# POESP32.net
KiCad netlist of a schematic drawn in EAGLE
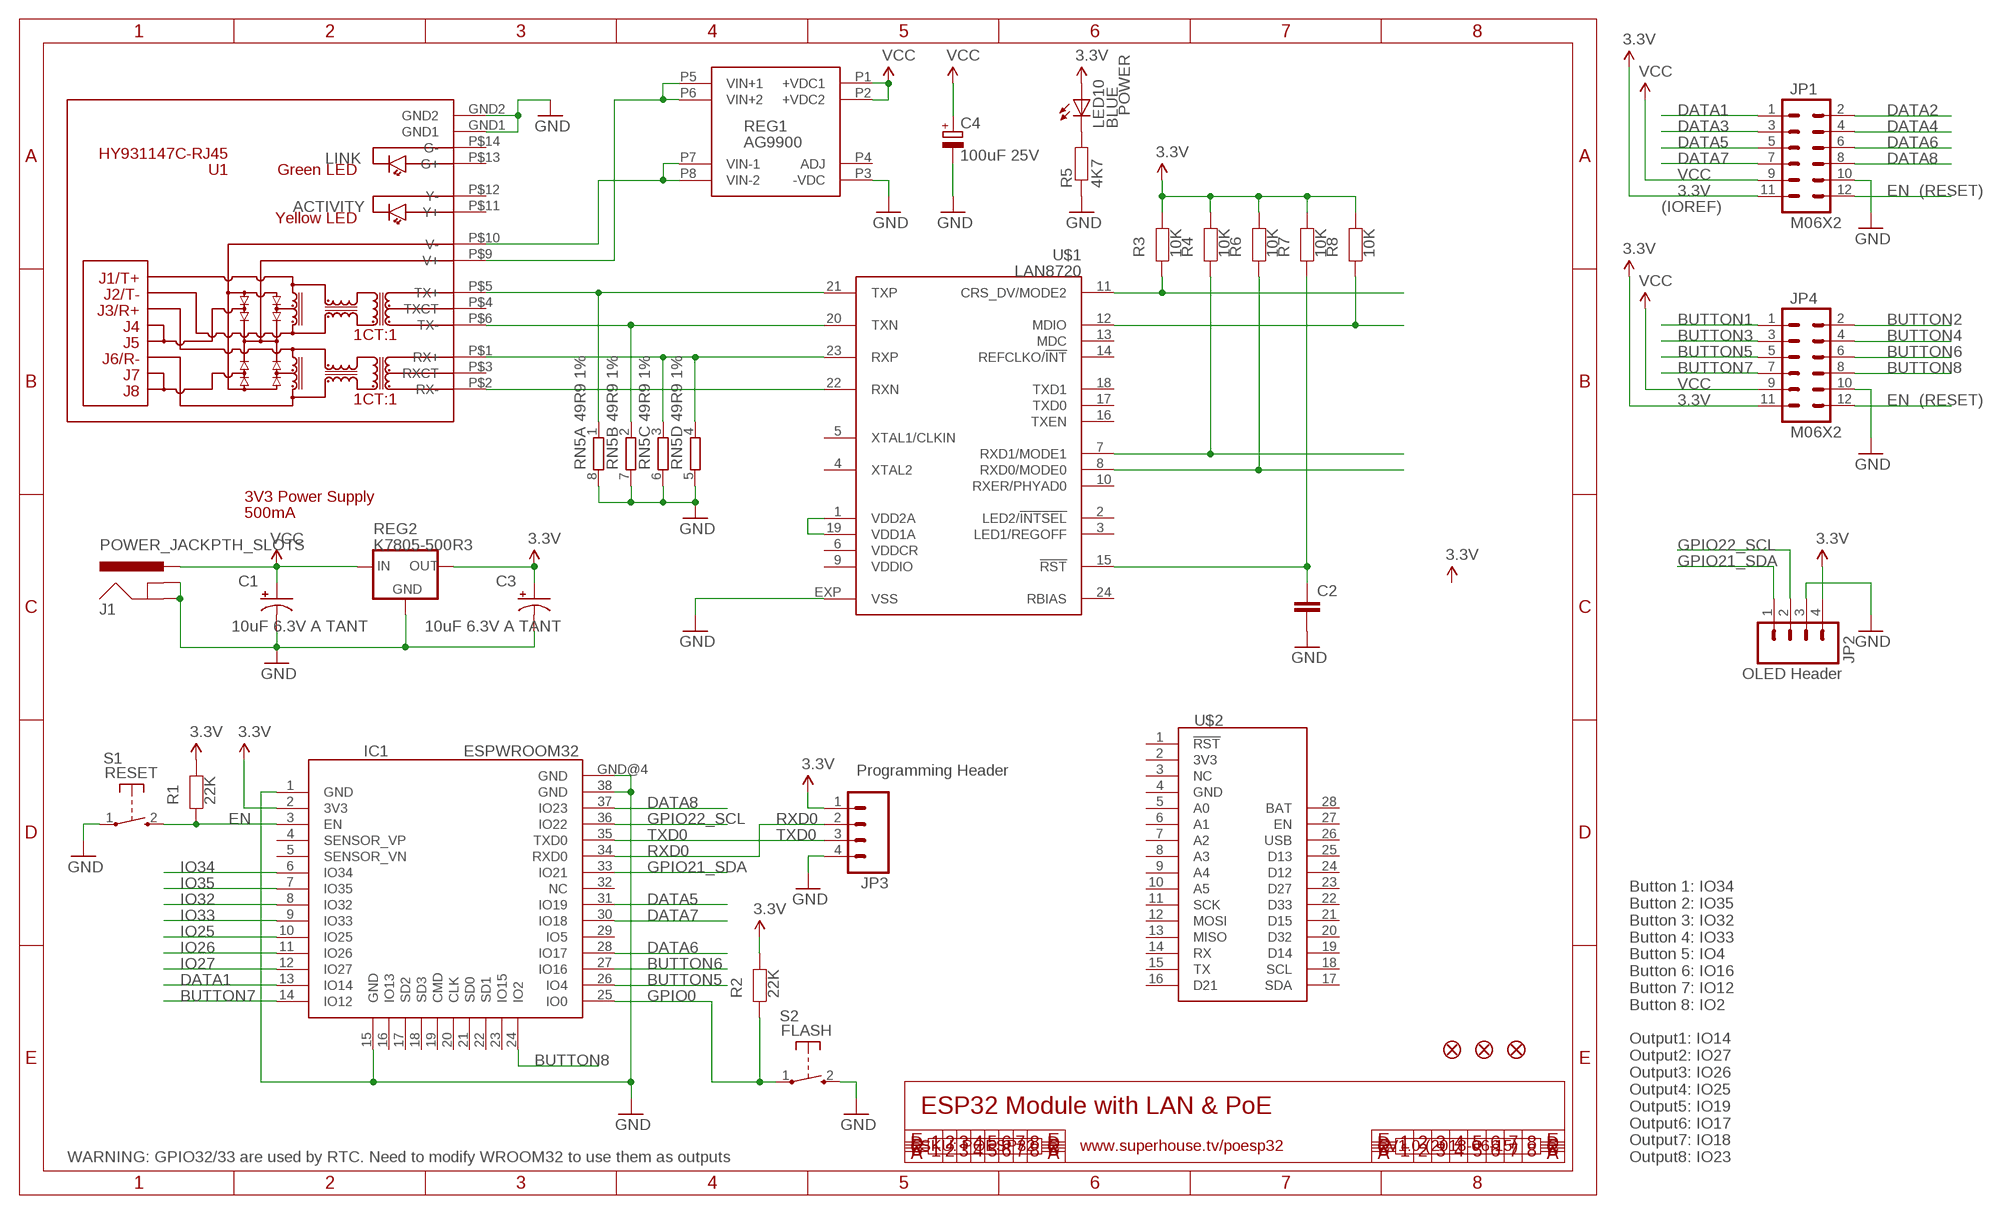
[diagram p0: schematic, sheet 1]

(export (version "E")
  (design (tool "Eeschema 10.0.6"))
  (components
    (comp (ref "C1")
      (value "10uF 6.3V A TANT")
      (footprint "eagle-import:EIA3216")
      (libsource (lib "eagle-import") (part "CAP_POL1206"))
    )
    (comp (ref "C2")
      (value "CAP0805")
      (footprint "eagle-import:0805")
      (libsource (lib "eagle-import") (part "CAP0805"))
    )
    (comp (ref "C3")
      (value "10uF 6.3V A TANT")
      (footprint "eagle-import:EIA3216")
      (libsource (lib "eagle-import") (part "CAP_POL1206"))
    )
    (comp (ref "C4")
      (value "100uF 25V")
      (footprint "eagle-import:PANASONIC_D")
      (libsource (lib "eagle-import") (part "CPOL-EUD"))
    )
    (comp (ref "FID1")
      (value "FIDUCIAL1X2.5")
      (footprint "eagle-import:FIDUCIAL-1X2.5")
      (libsource (lib "eagle-import") (part "FIDUCIAL1X2.5"))
    )
    (comp (ref "FID2")
      (value "FIDUCIAL1X2.5")
      (footprint "eagle-import:FIDUCIAL-1X2.5")
      (libsource (lib "eagle-import") (part "FIDUCIAL1X2.5"))
    )
    (comp (ref "FID3")
      (value "FIDUCIAL1X2.5")
      (footprint "eagle-import:FIDUCIAL-1X2.5")
      (libsource (lib "eagle-import") (part "FIDUCIAL1X2.5"))
    )
    (comp (ref "IC1")
      (value "ESPWROOM32")
      (footprint "eagle-import:ESPWROOM32")
      (libsource (lib "eagle-import") (part "ESPWROOM32"))
    )
    (comp (ref "J1")
      (value "POWER_JACKPTH_SLOTS")
      (footprint "eagle-import:POWER_JACK_PTH_SLOTS")
      (libsource (lib "eagle-import") (part "POWER_JACKPTH_SLOTS"))
    )
    (comp (ref "JP1")
      (value "M06X2")
      (footprint "eagle-import:2X6-SHROUDED")
      (libsource (lib "eagle-import") (part "M06X2"))
    )
    (comp (ref "JP2")
      (value "M04PTH")
      (footprint "eagle-import:1X04")
      (libsource (lib "eagle-import") (part "M04PTH"))
    )
    (comp (ref "JP3")
      (value "M04PTH")
      (footprint "eagle-import:1X04")
      (libsource (lib "eagle-import") (part "M04PTH"))
    )
    (comp (ref "JP4")
      (value "M06X2")
      (footprint "eagle-import:2X6-SHROUDED")
      (libsource (lib "eagle-import") (part "M06X2"))
    )
    (comp (ref "LED10")
      (value "BLUE")
      (footprint "eagle-import:LED-0603")
      (libsource (lib "eagle-import") (part "LED0603"))
    )
    (comp (ref "R1")
      (value "22K")
      (footprint "eagle-import:0603@2")
      (libsource (lib "eagle-import") (part "RESISTOR0603"))
    )
    (comp (ref "R2")
      (value "22K")
      (footprint "eagle-import:0603@2")
      (libsource (lib "eagle-import") (part "RESISTOR0603"))
    )
    (comp (ref "R3")
      (value "10K")
      (footprint "eagle-import:0603@2")
      (libsource (lib "eagle-import") (part "RESISTOR0603"))
    )
    (comp (ref "R4")
      (value "10K")
      (footprint "eagle-import:0603@2")
      (libsource (lib "eagle-import") (part "RESISTOR0603"))
    )
    (comp (ref "R5")
      (value "4K7")
      (footprint "eagle-import:0603")
      (libsource (lib "eagle-import") (part "freetronics-jon_RESISTOR0603"))
    )
    (comp (ref "R6")
      (value "10K")
      (footprint "eagle-import:0603@2")
      (libsource (lib "eagle-import") (part "RESISTOR0603"))
    )
    (comp (ref "R7")
      (value "10K")
      (footprint "eagle-import:0603@2")
      (libsource (lib "eagle-import") (part "RESISTOR0603"))
    )
    (comp (ref "R8")
      (value "10K")
      (footprint "eagle-import:0603@2")
      (libsource (lib "eagle-import") (part "RESISTOR0603"))
    )
    (comp (ref "REG1")
      (value "AG9900")
      (footprint "eagle-import:AG9900")
      (libsource (lib "eagle-import") (part "AG9900"))
    )
    (comp (ref "REG2")
      (value "K7805-500R3")
      (footprint "eagle-import:K78XX-500R3")
      (libsource (lib "eagle-import") (part "K78XX-500R3"))
    )
    (comp (ref "RN5")
      (value "49R9 1%")
      (footprint "eagle-import:CAY16")
      (libsource (lib "eagle-import") (part "4R-NCAY16"))
    )
    (comp (ref "S1")
      (value "RESET")
      (footprint "eagle-import:TACTILE_SWITCH_SMD_2PIN_TINY")
      (libsource (lib "eagle-import") (part "TAC_SWITCH_2PINSMT"))
    )
    (comp (ref "S2")
      (value "FLASH")
      (footprint "eagle-import:TACTILE_SWITCH_SMD_2PIN_TINY")
      (libsource (lib "eagle-import") (part "TAC_SWITCH_2PINSMT"))
    )
    (comp (ref "U$1")
      (value "LAN8720")
      (footprint "eagle-import:QFN24")
      (libsource (lib "eagle-import") (part "LAN8720"))
    )
    (comp (ref "U$2")
      (value "FEATHER")
      (footprint "eagle-import:FEATHER")
      (libsource (lib "eagle-import") (part "FEATHER"))
    )
    (comp (ref "U1")
      (value "HY931147C-RJ45")
      (footprint "eagle-import:HY931147C")
      (libsource (lib "eagle-import") (part "HY931147C-RJ45"))
    )
  )
  (nets
    (net (code "1") (name "/BUTTON1") (class "Default")
      (node (ref "JP4") (pin "1") (pinfunction "1_1") (pintype "passive"))
    )
    (net (code "2") (name "/BUTTON2") (class "Default")
      (node (ref "JP4") (pin "2") (pinfunction "2_2") (pintype "passive"))
    )
    (net (code "3") (name "/BUTTON3") (class "Default")
      (node (ref "JP4") (pin "3") (pinfunction "3_3") (pintype "passive"))
    )
    (net (code "4") (name "/BUTTON4") (class "Default")
      (node (ref "JP4") (pin "4") (pinfunction "4_4") (pintype "passive"))
    )
    (net (code "5") (name "/BUTTON5") (class "Default")
      (node (ref "IC1") (pin "26") (pinfunction "IO4_26") (pintype "bidirectional"))
      (node (ref "JP4") (pin "5") (pinfunction "5_5") (pintype "passive"))
    )
    (net (code "6") (name "/BUTTON6") (class "Default")
      (node (ref "IC1") (pin "27") (pinfunction "IO16_27") (pintype "bidirectional"))
      (node (ref "JP4") (pin "6") (pinfunction "6_6") (pintype "passive"))
    )
    (net (code "7") (name "/BUTTON7") (class "Default")
      (node (ref "IC1") (pin "14") (pinfunction "IO12_14") (pintype "bidirectional"))
      (node (ref "JP4") (pin "7") (pinfunction "7_7") (pintype "passive"))
    )
    (net (code "8") (name "/BUTTON8") (class "Default")
      (node (ref "IC1") (pin "24") (pinfunction "IO2_24") (pintype "bidirectional"))
      (node (ref "JP4") (pin "8") (pinfunction "8_8") (pintype "passive"))
    )
    (net (code "9") (name "/DATA1") (class "Default")
      (node (ref "IC1") (pin "13") (pinfunction "IO14_13") (pintype "bidirectional"))
      (node (ref "JP1") (pin "1") (pinfunction "1_1") (pintype "passive"))
    )
    (net (code "10") (name "/DATA2") (class "Default")
      (node (ref "JP1") (pin "2") (pinfunction "2_2") (pintype "passive"))
    )
    (net (code "11") (name "/DATA3") (class "Default")
      (node (ref "JP1") (pin "3") (pinfunction "3_3") (pintype "passive"))
    )
    (net (code "12") (name "/DATA4") (class "Default")
      (node (ref "JP1") (pin "4") (pinfunction "4_4") (pintype "passive"))
    )
    (net (code "13") (name "/DATA5") (class "Default")
      (node (ref "IC1") (pin "31") (pinfunction "IO19_31") (pintype "bidirectional"))
      (node (ref "JP1") (pin "5") (pinfunction "5_5") (pintype "passive"))
    )
    (net (code "14") (name "/DATA6") (class "Default")
      (node (ref "IC1") (pin "28") (pinfunction "IO17_28") (pintype "bidirectional"))
      (node (ref "JP1") (pin "6") (pinfunction "6_6") (pintype "passive"))
    )
    (net (code "15") (name "/DATA7") (class "Default")
      (node (ref "IC1") (pin "30") (pinfunction "IO18_30") (pintype "bidirectional"))
      (node (ref "JP1") (pin "7") (pinfunction "7_7") (pintype "passive"))
    )
    (net (code "16") (name "/DATA8") (class "Default")
      (node (ref "IC1") (pin "37") (pinfunction "IO23_37") (pintype "bidirectional"))
      (node (ref "JP1") (pin "8") (pinfunction "8_8") (pintype "passive"))
    )
    (net (code "17") (name "/EN") (class "Default")
      (node (ref "IC1") (pin "3") (pinfunction "EN_3") (pintype "bidirectional"))
      (node (ref "JP1") (pin "12") (pinfunction "12_12") (pintype "passive"))
      (node (ref "JP4") (pin "12") (pinfunction "12_12") (pintype "passive"))
      (node (ref "R1") (pin "2") (pinfunction "2_2") (pintype "passive"))
      (node (ref "S1") (pin "2") (pinfunction "S_2") (pintype "passive"))
    )
    (net (code "18") (name "/GPIO0") (class "Default")
      (node (ref "IC1") (pin "25") (pinfunction "IO0_25") (pintype "bidirectional"))
      (node (ref "R2") (pin "2") (pinfunction "2_2") (pintype "passive"))
      (node (ref "S2") (pin "1") (pinfunction "P_1") (pintype "passive"))
    )
    (net (code "19") (name "/GPIO21_SDA") (class "Default")
      (node (ref "IC1") (pin "33") (pinfunction "IO21_33") (pintype "bidirectional"))
      (node (ref "JP2") (pin "1") (pinfunction "1_1") (pintype "passive"))
    )
    (net (code "20") (name "/GPIO22_SCL") (class "Default")
      (node (ref "IC1") (pin "36") (pinfunction "IO22_36") (pintype "bidirectional"))
      (node (ref "JP2") (pin "2") (pinfunction "2_2") (pintype "passive"))
    )
    (net (code "21") (name "/IO25") (class "Default")
      (node (ref "IC1") (pin "10") (pinfunction "IO25_10") (pintype "bidirectional"))
    )
    (net (code "22") (name "/IO26") (class "Default")
      (node (ref "IC1") (pin "11") (pinfunction "IO26_11") (pintype "bidirectional"))
    )
    (net (code "23") (name "/IO27") (class "Default")
      (node (ref "IC1") (pin "12") (pinfunction "IO27_12") (pintype "bidirectional"))
    )
    (net (code "24") (name "/IO32") (class "Default")
      (node (ref "IC1") (pin "8") (pinfunction "IO32_8") (pintype "bidirectional"))
    )
    (net (code "25") (name "/IO33") (class "Default")
      (node (ref "IC1") (pin "9") (pinfunction "IO33_9") (pintype "bidirectional"))
    )
    (net (code "26") (name "/IO34") (class "Default")
      (node (ref "IC1") (pin "6") (pinfunction "IO34_6") (pintype "bidirectional"))
    )
    (net (code "27") (name "/IO35") (class "Default")
      (node (ref "IC1") (pin "7") (pinfunction "IO35_7") (pintype "bidirectional"))
    )
    (net (code "28") (name "/RXD0") (class "Default")
      (node (ref "IC1") (pin "34") (pinfunction "RXD0_34") (pintype "bidirectional"))
      (node (ref "JP3") (pin "2") (pinfunction "2_2") (pintype "passive"))
    )
    (net (code "29") (name "/TXD0") (class "Default")
      (node (ref "IC1") (pin "35") (pinfunction "TXD0_35") (pintype "bidirectional"))
      (node (ref "JP3") (pin "3") (pinfunction "3_3") (pintype "passive"))
    )
    (net (code "30") (name "/VDDCR") (class "Default")
      (node (ref "U$1") (pin "6") (pinfunction "VDDCR_6") (pintype "power_in"))
    )
    (net (code "31") (name "/VDDIO") (class "Default")
      (node (ref "U$1") (pin "9") (pinfunction "VDDIO_9") (pintype "power_in"))
    )
    (net (code "32") (name "3.3V") (class "Default")
      (node (ref "C3") (pin "A") (pinfunction "+_A") (pintype "passive"))
      (node (ref "IC1") (pin "2") (pinfunction "3V3_2") (pintype "power_in"))
      (node (ref "JP1") (pin "11") (pinfunction "11_11") (pintype "passive"))
      (node (ref "JP2") (pin "4") (pinfunction "4_4") (pintype "passive"))
      (node (ref "JP3") (pin "1") (pinfunction "1_1") (pintype "passive"))
      (node (ref "JP4") (pin "11") (pinfunction "11_11") (pintype "passive"))
      (node (ref "LED10") (pin "A") (pinfunction "A_A") (pintype "passive"))
      (node (ref "R1") (pin "1") (pinfunction "1_1") (pintype "passive"))
      (node (ref "R2") (pin "1") (pinfunction "1_1") (pintype "passive"))
      (node (ref "R3") (pin "1") (pinfunction "1_1") (pintype "passive"))
      (node (ref "R4") (pin "1") (pinfunction "1_1") (pintype "passive"))
      (node (ref "R6") (pin "1") (pinfunction "1_1") (pintype "passive"))
      (node (ref "R7") (pin "1") (pinfunction "1_1") (pintype "passive"))
      (node (ref "R8") (pin "1") (pinfunction "1_1") (pintype "passive"))
      (node (ref "REG2") (pin "3") (pinfunction "OUT_3") (pintype "output"))
    )
    (net (code "33") (name "GND") (class "Default")
      (node (ref "C1") (pin "C") (pinfunction "-_C") (pintype "passive"))
      (node (ref "C2") (pin "2") (pinfunction "2_2") (pintype "passive"))
      (node (ref "C3") (pin "C") (pinfunction "-_C") (pintype "passive"))
      (node (ref "C4") (pin "-") (pinfunction "-_-") (pintype "passive"))
      (node (ref "IC1") (pin "1") (pinfunction "GND_1") (pintype "power_in"))
      (node (ref "IC1") (pin "15") (pinfunction "GND_15") (pintype "power_in"))
      (node (ref "IC1") (pin "38") (pinfunction "GND_38") (pintype "power_in"))
      (node (ref "IC1") (pin "GND@4") (pinfunction "GND_GND@4") (pintype "power_in"))
      (node (ref "J1") (pin "GND") (pinfunction "GND_GND") (pintype "bidirectional"))
      (node (ref "J1") (pin "GNDBREAK") (pinfunction "GNDBREAK_GNDBREAK") (pintype "bidirectional"))
      (node (ref "JP1") (pin "10") (pinfunction "10_10") (pintype "passive"))
      (node (ref "JP2") (pin "3") (pinfunction "3_3") (pintype "passive"))
      (node (ref "JP3") (pin "4") (pinfunction "4_4") (pintype "passive"))
      (node (ref "JP4") (pin "10") (pinfunction "10_10") (pintype "passive"))
      (node (ref "R5") (pin "1") (pinfunction "1_1") (pintype "passive"))
      (node (ref "REG1") (pin "P3") (pinfunction "-VDC_P3") (pintype "bidirectional"))
      (node (ref "REG2") (pin "2") (pinfunction "GND_2") (pintype "input"))
      (node (ref "RN5") (pin "5") (pinfunction "2_5") (pintype "passive"))
      (node (ref "RN5") (pin "6") (pinfunction "2_6") (pintype "passive"))
      (node (ref "RN5") (pin "7") (pinfunction "2_7") (pintype "passive"))
      (node (ref "RN5") (pin "8") (pinfunction "2_8") (pintype "passive"))
      (node (ref "S1") (pin "1") (pinfunction "P_1") (pintype "passive"))
      (node (ref "S2") (pin "2") (pinfunction "S_2") (pintype "passive"))
      (node (ref "U$1") (pin "EXP") (pinfunction "VSS_EXP") (pintype "power_in"))
      (node (ref "U1") (pin "GND1") (pinfunction "GND1_GND1") (pintype "bidirectional"))
      (node (ref "U1") (pin "GND2") (pinfunction "GND2_GND2") (pintype "bidirectional"))
    )
    (net (code "34") (name "Net-(LED10-PadC)") (class "Default")
      (node (ref "LED10") (pin "C") (pinfunction "C_C") (pintype "passive"))
      (node (ref "R5") (pin "2") (pinfunction "2_2") (pintype "passive"))
    )
    (net (code "35") (name "Net-(REG1-VIN+1)") (class "Default")
      (node (ref "REG1") (pin "P5") (pinfunction "VIN+1_P5") (pintype "power_in"))
      (node (ref "REG1") (pin "P6") (pinfunction "VIN+2_P6") (pintype "power_in"))
      (node (ref "U1") (pin "P$9") (pinfunction "V+_P$9") (pintype "bidirectional"))
    )
    (net (code "36") (name "Net-(REG1-VIN-1)") (class "Default")
      (node (ref "REG1") (pin "P7") (pinfunction "VIN-1_P7") (pintype "power_in"))
      (node (ref "REG1") (pin "P8") (pinfunction "VIN-2_P8") (pintype "power_in"))
      (node (ref "U1") (pin "P$10") (pinfunction "V-_P$10") (pintype "bidirectional"))
    )
    (net (code "37") (name "Net-(RN5B-1)") (class "Default")
      (node (ref "RN5") (pin "2") (pinfunction "1_2") (pintype "passive"))
      (node (ref "U$1") (pin "20") (pinfunction "TXN_20") (pintype "bidirectional"))
      (node (ref "U1") (pin "P$6") (pinfunction "TX-_P$6") (pintype "bidirectional"))
    )
    (net (code "38") (name "Net-(RN5C-1)") (class "Default")
      (node (ref "RN5") (pin "3") (pinfunction "1_3") (pintype "passive"))
      (node (ref "RN5") (pin "4") (pinfunction "1_4") (pintype "passive"))
      (node (ref "U$1") (pin "23") (pinfunction "RXP_23") (pintype "bidirectional"))
      (node (ref "U1") (pin "P$1") (pinfunction "RX+_P$1") (pintype "bidirectional"))
    )
    (net (code "39") (name "Net-(U$1-CRS_DV{slash}MODE2)") (class "Default")
      (node (ref "R3") (pin "2") (pinfunction "2_2") (pintype "passive"))
      (node (ref "U$1") (pin "11") (pinfunction "CRS_DV/MODE2_11") (pintype "bidirectional"))
    )
    (net (code "40") (name "Net-(U$1-MDIO)") (class "Default")
      (node (ref "R8") (pin "2") (pinfunction "2_2") (pintype "passive"))
      (node (ref "U$1") (pin "12") (pinfunction "MDIO_12") (pintype "bidirectional"))
    )
    (net (code "41") (name "Net-(U$1-RXD0{slash}MODE0)") (class "Default")
      (node (ref "R6") (pin "2") (pinfunction "2_2") (pintype "passive"))
      (node (ref "U$1") (pin "8") (pinfunction "RXD0/MODE0_8") (pintype "bidirectional"))
    )
    (net (code "42") (name "Net-(U$1-RXD1{slash}MODE1)") (class "Default")
      (node (ref "R4") (pin "2") (pinfunction "2_2") (pintype "passive"))
      (node (ref "U$1") (pin "7") (pinfunction "RXD1/MODE1_7") (pintype "bidirectional"))
    )
    (net (code "43") (name "Net-(U$1-RXN)") (class "Default")
      (node (ref "U$1") (pin "22") (pinfunction "RXN_22") (pintype "bidirectional"))
      (node (ref "U1") (pin "P$2") (pinfunction "RX-_P$2") (pintype "bidirectional"))
    )
    (net (code "44") (name "Net-(U$1-TXP)") (class "Default")
      (node (ref "RN5") (pin "1") (pinfunction "1_1") (pintype "passive"))
      (node (ref "U$1") (pin "21") (pinfunction "TXP_21") (pintype "bidirectional"))
      (node (ref "U1") (pin "P$5") (pinfunction "TX+_P$5") (pintype "bidirectional"))
    )
    (net (code "45") (name "Net-(U$1-VDD1A)") (class "Default")
      (node (ref "U$1") (pin "1") (pinfunction "VDD2A_1") (pintype "power_in"))
      (node (ref "U$1") (pin "19") (pinfunction "VDD1A_19") (pintype "power_in"))
    )
    (net (code "46") (name "Net-(U$1-~{RST})") (class "Default")
      (node (ref "C2") (pin "1") (pinfunction "1_1") (pintype "passive"))
      (node (ref "R7") (pin "2") (pinfunction "2_2") (pintype "passive"))
      (node (ref "U$1") (pin "15") (pinfunction "~{RST}_15") (pintype "bidirectional"))
    )
    (net (code "47") (name "VCC") (class "Default")
      (node (ref "C1") (pin "A") (pinfunction "+_A") (pintype "passive"))
      (node (ref "C4") (pin "+") (pinfunction "+_+") (pintype "passive"))
      (node (ref "J1") (pin "PWR") (pinfunction "PWR_PWR") (pintype "bidirectional"))
      (node (ref "JP1") (pin "9") (pinfunction "9_9") (pintype "passive"))
      (node (ref "JP4") (pin "9") (pinfunction "9_9") (pintype "passive"))
      (node (ref "REG1") (pin "P1") (pinfunction "+VDC1_P1") (pintype "bidirectional"))
      (node (ref "REG1") (pin "P2") (pinfunction "+VDC2_P2") (pintype "bidirectional"))
      (node (ref "REG2") (pin "1") (pinfunction "IN_1") (pintype "input"))
    )
    (net (code "48") (name "unconnected-(IC1-CLK-Pad20)") (class "Default")
      (node (ref "IC1") (pin "20") (pinfunction "CLK_20") (pintype "bidirectional"))
    )
    (net (code "49") (name "unconnected-(IC1-CMD-Pad19)") (class "Default")
      (node (ref "IC1") (pin "19") (pinfunction "CMD_19") (pintype "bidirectional"))
    )
    (net (code "50") (name "unconnected-(IC1-IO5-Pad29)") (class "Default")
      (node (ref "IC1") (pin "29") (pinfunction "IO5_29") (pintype "bidirectional"))
    )
    (net (code "51") (name "unconnected-(IC1-IO13-Pad16)") (class "Default")
      (node (ref "IC1") (pin "16") (pinfunction "IO13_16") (pintype "bidirectional"))
    )
    (net (code "52") (name "unconnected-(IC1-IO15-Pad23)") (class "Default")
      (node (ref "IC1") (pin "23") (pinfunction "IO15_23") (pintype "bidirectional"))
    )
    (net (code "53") (name "unconnected-(IC1-NC-Pad32)") (class "Default")
      (node (ref "IC1") (pin "32") (pinfunction "NC_32") (pintype "bidirectional"))
    )
    (net (code "54") (name "unconnected-(IC1-SD0-Pad21)") (class "Default")
      (node (ref "IC1") (pin "21") (pinfunction "SD0_21") (pintype "bidirectional"))
    )
    (net (code "55") (name "unconnected-(IC1-SD1-Pad22)") (class "Default")
      (node (ref "IC1") (pin "22") (pinfunction "SD1_22") (pintype "bidirectional"))
    )
    (net (code "56") (name "unconnected-(IC1-SD2-Pad17)") (class "Default")
      (node (ref "IC1") (pin "17") (pinfunction "SD2_17") (pintype "bidirectional"))
    )
    (net (code "57") (name "unconnected-(IC1-SD3-Pad18)") (class "Default")
      (node (ref "IC1") (pin "18") (pinfunction "SD3_18") (pintype "bidirectional"))
    )
    (net (code "58") (name "unconnected-(IC1-SENSOR_VN-Pad5)") (class "Default")
      (node (ref "IC1") (pin "5") (pinfunction "SENSOR_VN_5") (pintype "bidirectional"))
    )
    (net (code "59") (name "unconnected-(IC1-SENSOR_VP-Pad4)") (class "Default")
      (node (ref "IC1") (pin "4") (pinfunction "SENSOR_VP_4") (pintype "bidirectional"))
    )
    (net (code "60") (name "unconnected-(REG1-ADJ-PadP4)") (class "Default")
      (node (ref "REG1") (pin "P4") (pinfunction "ADJ_P4") (pintype "input"))
    )
    (net (code "61") (name "unconnected-(U$1-LED1{slash}REGOFF-Pad3)") (class "Default")
      (node (ref "U$1") (pin "3") (pinfunction "LED1/REGOFF_3") (pintype "bidirectional"))
    )
    (net (code "62") (name "unconnected-(U$1-LED2{slash}~{INTSEL}-Pad2)") (class "Default")
      (node (ref "U$1") (pin "2") (pinfunction "LED2/~{INTSEL}_2") (pintype "bidirectional"))
    )
    (net (code "63") (name "unconnected-(U$1-MDC-Pad13)") (class "Default")
      (node (ref "U$1") (pin "13") (pinfunction "MDC_13") (pintype "bidirectional"))
    )
    (net (code "64") (name "unconnected-(U$1-RBIAS-Pad24)") (class "Default")
      (node (ref "U$1") (pin "24") (pinfunction "RBIAS_24") (pintype "bidirectional"))
    )
    (net (code "65") (name "unconnected-(U$1-REFCLKO{slash}~{INT}-Pad14)") (class "Default")
      (node (ref "U$1") (pin "14") (pinfunction "REFCLKO/~{INT}_14") (pintype "bidirectional"))
    )
    (net (code "66") (name "unconnected-(U$1-RXER{slash}PHYAD0-Pad10)") (class "Default")
      (node (ref "U$1") (pin "10") (pinfunction "RXER/PHYAD0_10") (pintype "bidirectional"))
    )
    (net (code "67") (name "unconnected-(U$1-TXD0-Pad17)") (class "Default")
      (node (ref "U$1") (pin "17") (pinfunction "TXD0_17") (pintype "bidirectional"))
    )
    (net (code "68") (name "unconnected-(U$1-TXD1-Pad18)") (class "Default")
      (node (ref "U$1") (pin "18") (pinfunction "TXD1_18") (pintype "bidirectional"))
    )
    (net (code "69") (name "unconnected-(U$1-TXEN-Pad16)") (class "Default")
      (node (ref "U$1") (pin "16") (pinfunction "TXEN_16") (pintype "bidirectional"))
    )
    (net (code "70") (name "unconnected-(U$1-XTAL1{slash}CLKIN-Pad5)") (class "Default")
      (node (ref "U$1") (pin "5") (pinfunction "XTAL1/CLKIN_5") (pintype "bidirectional"))
    )
    (net (code "71") (name "unconnected-(U$1-XTAL2-Pad4)") (class "Default")
      (node (ref "U$1") (pin "4") (pinfunction "XTAL2_4") (pintype "bidirectional"))
    )
    (net (code "72") (name "unconnected-(U$2-3V3-Pad2)") (class "Default")
      (node (ref "U$2") (pin "2") (pinfunction "3V3_2") (pintype "bidirectional"))
    )
    (net (code "73") (name "unconnected-(U$2-A0-Pad5)") (class "Default")
      (node (ref "U$2") (pin "5") (pinfunction "A0_5") (pintype "bidirectional"))
    )
    (net (code "74") (name "unconnected-(U$2-A1-Pad6)") (class "Default")
      (node (ref "U$2") (pin "6") (pinfunction "A1_6") (pintype "bidirectional"))
    )
    (net (code "75") (name "unconnected-(U$2-A2-Pad7)") (class "Default")
      (node (ref "U$2") (pin "7") (pinfunction "A2_7") (pintype "bidirectional"))
    )
    (net (code "76") (name "unconnected-(U$2-A3-Pad8)") (class "Default")
      (node (ref "U$2") (pin "8") (pinfunction "A3_8") (pintype "bidirectional"))
    )
    (net (code "77") (name "unconnected-(U$2-A4-Pad9)") (class "Default")
      (node (ref "U$2") (pin "9") (pinfunction "A4_9") (pintype "bidirectional"))
    )
    (net (code "78") (name "unconnected-(U$2-A5-Pad10)") (class "Default")
      (node (ref "U$2") (pin "10") (pinfunction "A5_10") (pintype "bidirectional"))
    )
    (net (code "79") (name "unconnected-(U$2-BAT-Pad28)") (class "Default")
      (node (ref "U$2") (pin "28") (pinfunction "BAT_28") (pintype "bidirectional"))
    )
    (net (code "80") (name "unconnected-(U$2-D12-Pad24)") (class "Default")
      (node (ref "U$2") (pin "24") (pinfunction "D12_24") (pintype "bidirectional"))
    )
    (net (code "81") (name "unconnected-(U$2-D13-Pad25)") (class "Default")
      (node (ref "U$2") (pin "25") (pinfunction "D13_25") (pintype "bidirectional"))
    )
    (net (code "82") (name "unconnected-(U$2-D14-Pad19)") (class "Default")
      (node (ref "U$2") (pin "19") (pinfunction "D14_19") (pintype "bidirectional"))
    )
    (net (code "83") (name "unconnected-(U$2-D15-Pad21)") (class "Default")
      (node (ref "U$2") (pin "21") (pinfunction "D15_21") (pintype "bidirectional"))
    )
    (net (code "84") (name "unconnected-(U$2-D21-Pad16)") (class "Default")
      (node (ref "U$2") (pin "16") (pinfunction "D21_16") (pintype "bidirectional"))
    )
    (net (code "85") (name "unconnected-(U$2-D27-Pad23)") (class "Default")
      (node (ref "U$2") (pin "23") (pinfunction "D27_23") (pintype "bidirectional"))
    )
    (net (code "86") (name "unconnected-(U$2-D32-Pad20)") (class "Default")
      (node (ref "U$2") (pin "20") (pinfunction "D32_20") (pintype "bidirectional"))
    )
    (net (code "87") (name "unconnected-(U$2-D33-Pad22)") (class "Default")
      (node (ref "U$2") (pin "22") (pinfunction "D33_22") (pintype "bidirectional"))
    )
    (net (code "88") (name "unconnected-(U$2-EN-Pad27)") (class "Default")
      (node (ref "U$2") (pin "27") (pinfunction "EN_27") (pintype "bidirectional"))
    )
    (net (code "89") (name "unconnected-(U$2-GND-Pad4)") (class "Default")
      (node (ref "U$2") (pin "4") (pinfunction "GND_4") (pintype "bidirectional"))
    )
    (net (code "90") (name "unconnected-(U$2-MISO-Pad13)") (class "Default")
      (node (ref "U$2") (pin "13") (pinfunction "MISO_13") (pintype "bidirectional"))
    )
    (net (code "91") (name "unconnected-(U$2-MOSI-Pad12)") (class "Default")
      (node (ref "U$2") (pin "12") (pinfunction "MOSI_12") (pintype "bidirectional"))
    )
    (net (code "92") (name "unconnected-(U$2-NC-Pad3)") (class "Default")
      (node (ref "U$2") (pin "3") (pinfunction "NC_3") (pintype "bidirectional"))
    )
    (net (code "93") (name "unconnected-(U$2-RX-Pad14)") (class "Default")
      (node (ref "U$2") (pin "14") (pinfunction "RX_14") (pintype "bidirectional"))
    )
    (net (code "94") (name "unconnected-(U$2-SCK-Pad11)") (class "Default")
      (node (ref "U$2") (pin "11") (pinfunction "SCK_11") (pintype "bidirectional"))
    )
    (net (code "95") (name "unconnected-(U$2-SCL-Pad18)") (class "Default")
      (node (ref "U$2") (pin "18") (pinfunction "SCL_18") (pintype "bidirectional"))
    )
    (net (code "96") (name "unconnected-(U$2-SDA-Pad17)") (class "Default")
      (node (ref "U$2") (pin "17") (pinfunction "SDA_17") (pintype "bidirectional"))
    )
    (net (code "97") (name "unconnected-(U$2-TX-Pad15)") (class "Default")
      (node (ref "U$2") (pin "15") (pinfunction "TX_15") (pintype "bidirectional"))
    )
    (net (code "98") (name "unconnected-(U$2-USB-Pad26)") (class "Default")
      (node (ref "U$2") (pin "26") (pinfunction "USB_26") (pintype "bidirectional"))
    )
    (net (code "99") (name "unconnected-(U$2-~{RST}-Pad1)") (class "Default")
      (node (ref "U$2") (pin "1") (pinfunction "~{RST}_1") (pintype "bidirectional"))
    )
    (net (code "100") (name "unconnected-(U1-G+-PadP$13)") (class "Default")
      (node (ref "U1") (pin "P$13") (pinfunction "G+_P$13") (pintype "bidirectional"))
    )
    (net (code "101") (name "unconnected-(U1-G--PadP$14)") (class "Default")
      (node (ref "U1") (pin "P$14") (pinfunction "G-_P$14") (pintype "bidirectional"))
    )
    (net (code "102") (name "unconnected-(U1-RXCT-PadP$3)") (class "Default")
      (node (ref "U1") (pin "P$3") (pinfunction "RXCT_P$3") (pintype "bidirectional"))
    )
    (net (code "103") (name "unconnected-(U1-TXCT-PadP$4)") (class "Default")
      (node (ref "U1") (pin "P$4") (pinfunction "TXCT_P$4") (pintype "bidirectional"))
    )
    (net (code "104") (name "unconnected-(U1-Y+-PadP$11)") (class "Default")
      (node (ref "U1") (pin "P$11") (pinfunction "Y+_P$11") (pintype "bidirectional"))
    )
    (net (code "105") (name "unconnected-(U1-Y--PadP$12)") (class "Default")
      (node (ref "U1") (pin "P$12") (pinfunction "Y-_P$12") (pintype "bidirectional"))
    )
  )
)
